# lfoprime-7-25-21--LONG.net
KiCad netlist of a schematic drawn in EAGLE
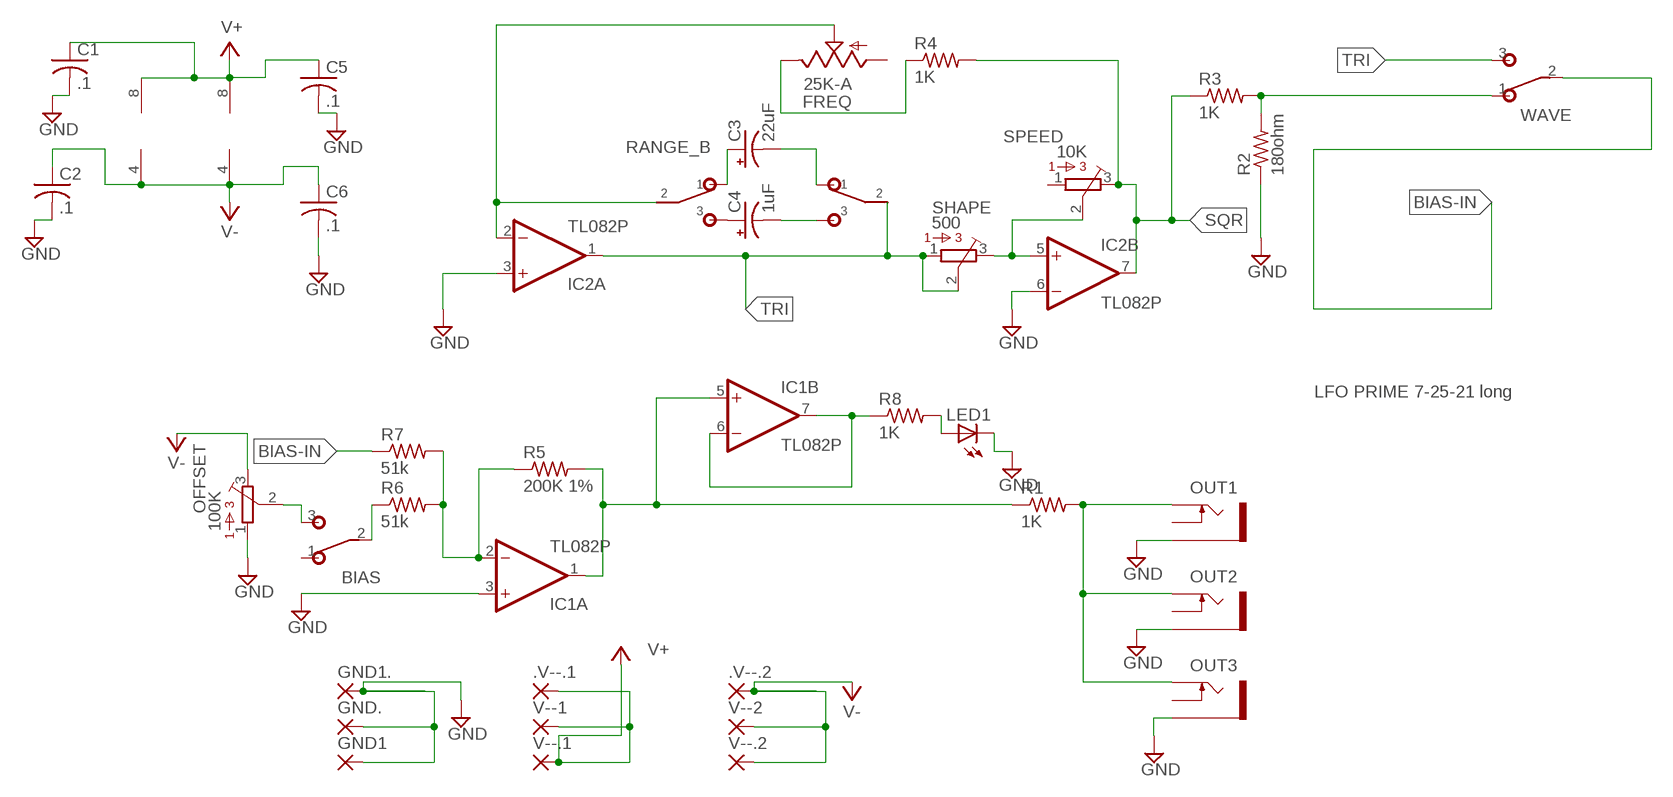
[diagram p0: schematic, sheet 1]

(export (version "E")
  (design (tool "Eeschema 10.0.6"))
  (components
    (comp (ref ".V--.1")
      (value "3,17/1,3")
      (footprint "eagle-import:3,17_1,3")
      (libsource (lib "eagle-import") (part "3,17/1,3"))
    )
    (comp (ref ".V--.2")
      (value "3,17/1,3")
      (footprint "eagle-import:3,17_1,3")
      (libsource (lib "eagle-import") (part "3,17/1,3"))
    )
    (comp (ref "BIAS")
      (value "SPDTPADS")
      (footprint "eagle-import:SPDT")
      (libsource (lib "eagle-import") (part "SPDTPADS"))
    )
    (comp (ref "C1")
      (value ".1")
      (footprint "eagle-import:C025-025X050")
      (libsource (lib "eagle-import") (part "C-US025-025X050"))
    )
    (comp (ref "C2")
      (value ".1")
      (footprint "eagle-import:C025-025X050")
      (libsource (lib "eagle-import") (part "C-US025-025X050"))
    )
    (comp (ref "C3")
      (value "22uF")
      (footprint "eagle-import:E5-4")
      (libsource (lib "eagle-import") (part "CPOL-USE5-4"))
    )
    (comp (ref "C4")
      (value "1uF")
      (footprint "eagle-import:E5-4")
      (libsource (lib "eagle-import") (part "CPOL-USE5-4"))
    )
    (comp (ref "C5")
      (value ".1")
      (footprint "eagle-import:C025-025X050")
      (libsource (lib "eagle-import") (part "C-US025-025X050"))
    )
    (comp (ref "C6")
      (value ".1")
      (footprint "eagle-import:C025-025X050")
      (libsource (lib "eagle-import") (part "C-US025-025X050"))
    )
    (comp (ref "FREQ")
      (value "25K-A")
      (footprint "eagle-import:9MM_SNAP-IN_POT")
      (libsource (lib "eagle-import") (part "9MM_SNAP-IN_POT_"))
    )
    (comp (ref "GND.")
      (value "3,17/1,3")
      (footprint "eagle-import:3,17_1,3")
      (libsource (lib "eagle-import") (part "3,17/1,3"))
    )
    (comp (ref "GND1")
      (value "3,17/1,3")
      (footprint "eagle-import:3,17_1,3")
      (libsource (lib "eagle-import") (part "3,17/1,3"))
    )
    (comp (ref "GND1.")
      (value "3,17/1,3")
      (footprint "eagle-import:3,17_1,3")
      (libsource (lib "eagle-import") (part "3,17/1,3"))
    )
    (comp (ref "IC1")
      (value "TL082P")
      (footprint "eagle-import:DIL08")
      (libsource (lib "eagle-import") (part "TL082P"))
    )
    (comp (ref "IC2")
      (value "TL082P")
      (footprint "eagle-import:DIL08")
      (libsource (lib "eagle-import") (part "TL082P"))
    )
    (comp (ref "LED1")
      (value "LED3MM")
      (footprint "eagle-import:LED3MM")
      (libsource (lib "eagle-import") (part "LED3MM"))
    )
    (comp (ref "OFFSET")
      (value "100K")
      (footprint "eagle-import:3362H")
      (libsource (lib "eagle-import") (part "3362H"))
    )
    (comp (ref "OUT1")
      (value "THONKICONNNEW")
      (footprint "eagle-import:WQP-PJ301M-12_JACK")
      (libsource (lib "eagle-import") (part "THONKICONNNEW"))
    )
    (comp (ref "OUT2")
      (value "THONKICONNNEW")
      (footprint "eagle-import:WQP-PJ301M-12_JACK")
      (libsource (lib "eagle-import") (part "THONKICONNNEW"))
    )
    (comp (ref "OUT3")
      (value "THONKICONNNEW")
      (footprint "eagle-import:WQP-PJ301M-12_JACK")
      (libsource (lib "eagle-import") (part "THONKICONNNEW"))
    )
    (comp (ref "R1")
      (value "1K")
      (footprint "eagle-import:0204_7")
      (libsource (lib "eagle-import") (part "R-US_0204/7"))
    )
    (comp (ref "R2")
      (value "180ohm")
      (footprint "eagle-import:0204_7")
      (libsource (lib "eagle-import") (part "R-US_0204/7"))
    )
    (comp (ref "R3")
      (value "1K")
      (footprint "eagle-import:0204_7")
      (libsource (lib "eagle-import") (part "R-US_0204/7"))
    )
    (comp (ref "R4")
      (value "1K")
      (footprint "eagle-import:0204_7")
      (libsource (lib "eagle-import") (part "R-US_0204/7"))
    )
    (comp (ref "R5")
      (value "200K 1%")
      (footprint "eagle-import:0204_7")
      (libsource (lib "eagle-import") (part "R-US_0204/7"))
    )
    (comp (ref "R6")
      (value "51k")
      (footprint "eagle-import:0204_7")
      (libsource (lib "eagle-import") (part "R-US_0204/7"))
    )
    (comp (ref "R7")
      (value "51k")
      (footprint "eagle-import:0204_7")
      (libsource (lib "eagle-import") (part "R-US_0204/7"))
    )
    (comp (ref "R8")
      (value "1K")
      (footprint "eagle-import:0204_7")
      (libsource (lib "eagle-import") (part "R-US_0204/7"))
    )
    (comp (ref "RANGE")
      (value "DPDT-WIDE")
      (footprint "eagle-import:DPDT-WIDE")
      (libsource (lib "eagle-import") (part "DPDT-WIDE"))
    )
    (comp (ref "SHAPE")
      (value "500")
      (footprint "eagle-import:3362H")
      (libsource (lib "eagle-import") (part "3362H"))
    )
    (comp (ref "SPEED")
      (value "10K")
      (footprint "eagle-import:3362H")
      (libsource (lib "eagle-import") (part "3362H"))
    )
    (comp (ref "V--.1")
      (value "3,17/1,3")
      (footprint "eagle-import:3,17_1,3")
      (libsource (lib "eagle-import") (part "3,17/1,3"))
    )
    (comp (ref "V--.2")
      (value "3,17/1,3")
      (footprint "eagle-import:3,17_1,3")
      (libsource (lib "eagle-import") (part "3,17/1,3"))
    )
    (comp (ref "V--1")
      (value "3,17/1,3")
      (footprint "eagle-import:3,17_1,3")
      (libsource (lib "eagle-import") (part "3,17/1,3"))
    )
    (comp (ref "V--2")
      (value "3,17/1,3")
      (footprint "eagle-import:3,17_1,3")
      (libsource (lib "eagle-import") (part "3,17/1,3"))
    )
    (comp (ref "WAVE")
      (value "SPDTPADS")
      (footprint "eagle-import:SPDT")
      (libsource (lib "eagle-import") (part "SPDTPADS"))
    )
  )
  (nets
    (net (code "1") (name "BIAS-IN") (class "Default")
      (node (ref "R7") (pin "1") (pinfunction "1_1") (pintype "passive"))
      (node (ref "WAVE") (pin "2") (pinfunction "P_2") (pintype "passive"))
    )
    (net (code "2") (name "GND") (class "Default")
      (node (ref "C1") (pin "2") (pinfunction "2_2") (pintype "passive"))
      (node (ref "C2") (pin "2") (pinfunction "2_2") (pintype "passive"))
      (node (ref "C5") (pin "2") (pinfunction "2_2") (pintype "passive"))
      (node (ref "C6") (pin "2") (pinfunction "2_2") (pintype "passive"))
      (node (ref "GND.") (pin "1") (pinfunction "P_1") (pintype "passive"))
      (node (ref "GND1") (pin "1") (pinfunction "P_1") (pintype "passive"))
      (node (ref "GND1.") (pin "1") (pinfunction "P_1") (pintype "passive"))
      (node (ref "IC1") (pin "3") (pinfunction "+IN_3") (pintype "input"))
      (node (ref "IC2") (pin "3") (pinfunction "+IN_3") (pintype "input"))
      (node (ref "IC2") (pin "6") (pinfunction "-IN_6") (pintype "input"))
      (node (ref "LED1") (pin "K") (pinfunction "C_K") (pintype "passive"))
      (node (ref "OFFSET") (pin "1") (pinfunction "1_1") (pintype "passive"))
      (node (ref "OUT1") (pin "P$3_SLEEVE") (pinfunction "SLEEVE_P$3_SLEEVE") (pintype "passive"))
      (node (ref "OUT2") (pin "P$3_SLEEVE") (pinfunction "SLEEVE_P$3_SLEEVE") (pintype "passive"))
      (node (ref "OUT3") (pin "P$3_SLEEVE") (pinfunction "SLEEVE_P$3_SLEEVE") (pintype "passive"))
      (node (ref "R2") (pin "1") (pinfunction "1_1") (pintype "passive"))
    )
    (net (code "3") (name "Net-(BIAS-P)") (class "Default")
      (node (ref "BIAS") (pin "2") (pinfunction "P_2") (pintype "passive"))
      (node (ref "R6") (pin "1") (pinfunction "1_1") (pintype "passive"))
    )
    (net (code "4") (name "Net-(BIAS-S)") (class "Default")
      (node (ref "BIAS") (pin "3") (pinfunction "S_3") (pintype "passive"))
      (node (ref "OFFSET") (pin "2") (pinfunction "2_2") (pintype "passive"))
    )
    (net (code "5") (name "Net-(FREQ-E)") (class "Default")
      (node (ref "FREQ") (pin "3") (pinfunction "E_3") (pintype "passive"))
      (node (ref "R4") (pin "1") (pinfunction "1_1") (pintype "passive"))
    )
    (net (code "6") (name "Net-(FREQ-S)") (class "Default")
      (node (ref "FREQ") (pin "2") (pinfunction "S_2") (pintype "passive"))
      (node (ref "IC2") (pin "2") (pinfunction "-IN_2") (pintype "input"))
      (node (ref "RANGE") (pin "A2") (pinfunction "2_A2") (pintype "passive"))
    )
    (net (code "7") (name "Net-(IC1A--IN)") (class "Default")
      (node (ref "IC1") (pin "2") (pinfunction "-IN_2") (pintype "input"))
      (node (ref "R5") (pin "1") (pinfunction "1_1") (pintype "passive"))
      (node (ref "R6") (pin "2") (pinfunction "2_2") (pintype "passive"))
      (node (ref "R7") (pin "2") (pinfunction "2_2") (pintype "passive"))
    )
    (net (code "8") (name "Net-(IC1A-OUT)") (class "Default")
      (node (ref "IC1") (pin "1") (pinfunction "OUT_1") (pintype "output"))
      (node (ref "IC1") (pin "5") (pinfunction "+IN_5") (pintype "input"))
      (node (ref "R1") (pin "1") (pinfunction "1_1") (pintype "passive"))
      (node (ref "R5") (pin "2") (pinfunction "2_2") (pintype "passive"))
    )
    (net (code "9") (name "Net-(IC1B--IN)") (class "Default")
      (node (ref "IC1") (pin "6") (pinfunction "-IN_6") (pintype "input"))
      (node (ref "IC1") (pin "7") (pinfunction "OUT_7") (pintype "output"))
      (node (ref "R8") (pin "1") (pinfunction "1_1") (pintype "passive"))
    )
    (net (code "10") (name "Net-(IC2B-+IN)") (class "Default")
      (node (ref "IC2") (pin "5") (pinfunction "+IN_5") (pintype "input"))
      (node (ref "SHAPE") (pin "3") (pinfunction "3_3") (pintype "passive"))
      (node (ref "SPEED") (pin "2") (pinfunction "2_2") (pintype "passive"))
    )
    (net (code "11") (name "Net-(LED1-PadA)") (class "Default")
      (node (ref "LED1") (pin "A") (pinfunction "A_A") (pintype "passive"))
      (node (ref "R8") (pin "2") (pinfunction "2_2") (pintype "passive"))
    )
    (net (code "12") (name "Net-(OUT1-TIP)") (class "Default")
      (node (ref "OUT1") (pin "P$1_TIP") (pinfunction "TIP_P$1_TIP") (pintype "passive"))
      (node (ref "OUT2") (pin "P$1_TIP") (pinfunction "TIP_P$1_TIP") (pintype "passive"))
      (node (ref "OUT3") (pin "P$1_TIP") (pinfunction "TIP_P$1_TIP") (pintype "passive"))
      (node (ref "R1") (pin "2") (pinfunction "2_2") (pintype "passive"))
    )
    (net (code "13") (name "Net-(RANGEA-1)") (class "Default")
      (node (ref "C3") (pin "+") (pinfunction "+_+") (pintype "passive"))
      (node (ref "RANGE") (pin "A1") (pinfunction "1_A1") (pintype "passive"))
    )
    (net (code "14") (name "Net-(RANGEA-3)") (class "Default")
      (node (ref "C4") (pin "+") (pinfunction "+_+") (pintype "passive"))
      (node (ref "RANGE") (pin "A3") (pinfunction "3_A3") (pintype "passive"))
    )
    (net (code "15") (name "Net-(RANGEB-1)") (class "Default")
      (node (ref "C3") (pin "-") (pinfunction "-_-") (pintype "passive"))
      (node (ref "RANGE") (pin "B1") (pinfunction "1_B1") (pintype "passive"))
    )
    (net (code "16") (name "Net-(RANGEB-3)") (class "Default")
      (node (ref "C4") (pin "-") (pinfunction "-_-") (pintype "passive"))
      (node (ref "RANGE") (pin "B3") (pinfunction "3_B3") (pintype "passive"))
    )
    (net (code "17") (name "Net-(WAVE-O)") (class "Default")
      (node (ref "R2") (pin "2") (pinfunction "2_2") (pintype "passive"))
      (node (ref "R3") (pin "2") (pinfunction "2_2") (pintype "passive"))
      (node (ref "WAVE") (pin "1") (pinfunction "O_1") (pintype "passive"))
    )
    (net (code "18") (name "SQR") (class "Default")
      (node (ref "IC2") (pin "7") (pinfunction "OUT_7") (pintype "output"))
      (node (ref "R3") (pin "1") (pinfunction "1_1") (pintype "passive"))
      (node (ref "R4") (pin "2") (pinfunction "2_2") (pintype "passive"))
      (node (ref "SPEED") (pin "3") (pinfunction "3_3") (pintype "passive"))
    )
    (net (code "19") (name "TRI") (class "Default")
      (node (ref "IC2") (pin "1") (pinfunction "OUT_1") (pintype "output"))
      (node (ref "RANGE") (pin "B2") (pinfunction "2_B2") (pintype "passive"))
      (node (ref "SHAPE") (pin "1") (pinfunction "1_1") (pintype "passive"))
      (node (ref "SHAPE") (pin "2") (pinfunction "2_2") (pintype "passive"))
      (node (ref "WAVE") (pin "3") (pinfunction "S_3") (pintype "passive"))
    )
    (net (code "20") (name "V+") (class "Default")
      (node (ref ".V--.1") (pin "1") (pinfunction "P_1") (pintype "passive"))
      (node (ref "C1") (pin "1") (pinfunction "1_1") (pintype "passive"))
      (node (ref "C5") (pin "1") (pinfunction "1_1") (pintype "passive"))
      (node (ref "IC1") (pin "8") (pinfunction "V+_8") (pintype "power_in"))
      (node (ref "IC2") (pin "8") (pinfunction "V+_8") (pintype "power_in"))
      (node (ref "V--.1") (pin "1") (pinfunction "P_1") (pintype "passive"))
      (node (ref "V--1") (pin "1") (pinfunction "P_1") (pintype "passive"))
    )
    (net (code "21") (name "V-") (class "Default")
      (node (ref ".V--.2") (pin "1") (pinfunction "P_1") (pintype "passive"))
      (node (ref "C2") (pin "1") (pinfunction "1_1") (pintype "passive"))
      (node (ref "C6") (pin "1") (pinfunction "1_1") (pintype "passive"))
      (node (ref "IC1") (pin "4") (pinfunction "V-_4") (pintype "power_in"))
      (node (ref "IC2") (pin "4") (pinfunction "V-_4") (pintype "power_in"))
      (node (ref "OFFSET") (pin "3") (pinfunction "3_3") (pintype "passive"))
      (node (ref "V--.2") (pin "1") (pinfunction "P_1") (pintype "passive"))
      (node (ref "V--2") (pin "1") (pinfunction "P_1") (pintype "passive"))
    )
    (net (code "22") (name "unconnected-(BIAS-O-Pad1)") (class "Default")
      (node (ref "BIAS") (pin "1") (pinfunction "O_1") (pintype "passive"))
    )
    (net (code "23") (name "unconnected-(FREQ-A-Pad1)") (class "Default")
      (node (ref "FREQ") (pin "1") (pinfunction "A_1") (pintype "passive"))
    )
    (net (code "24") (name "unconnected-(OUT1-SWITCH-PadP$2_SWITCH)") (class "Default")
      (node (ref "OUT1") (pin "P$2_SWITCH") (pinfunction "SWITCH_P$2_SWITCH") (pintype "passive"))
    )
    (net (code "25") (name "unconnected-(OUT2-SWITCH-PadP$2_SWITCH)") (class "Default")
      (node (ref "OUT2") (pin "P$2_SWITCH") (pinfunction "SWITCH_P$2_SWITCH") (pintype "passive"))
    )
    (net (code "26") (name "unconnected-(OUT3-SWITCH-PadP$2_SWITCH)") (class "Default")
      (node (ref "OUT3") (pin "P$2_SWITCH") (pinfunction "SWITCH_P$2_SWITCH") (pintype "passive"))
    )
    (net (code "27") (name "unconnected-(SPEED-Pad1)") (class "Default")
      (node (ref "SPEED") (pin "1") (pinfunction "1_1") (pintype "passive"))
    )
  )
)
